# PowerSupply.net
KiCad netlist of a schematic drawn in EAGLE
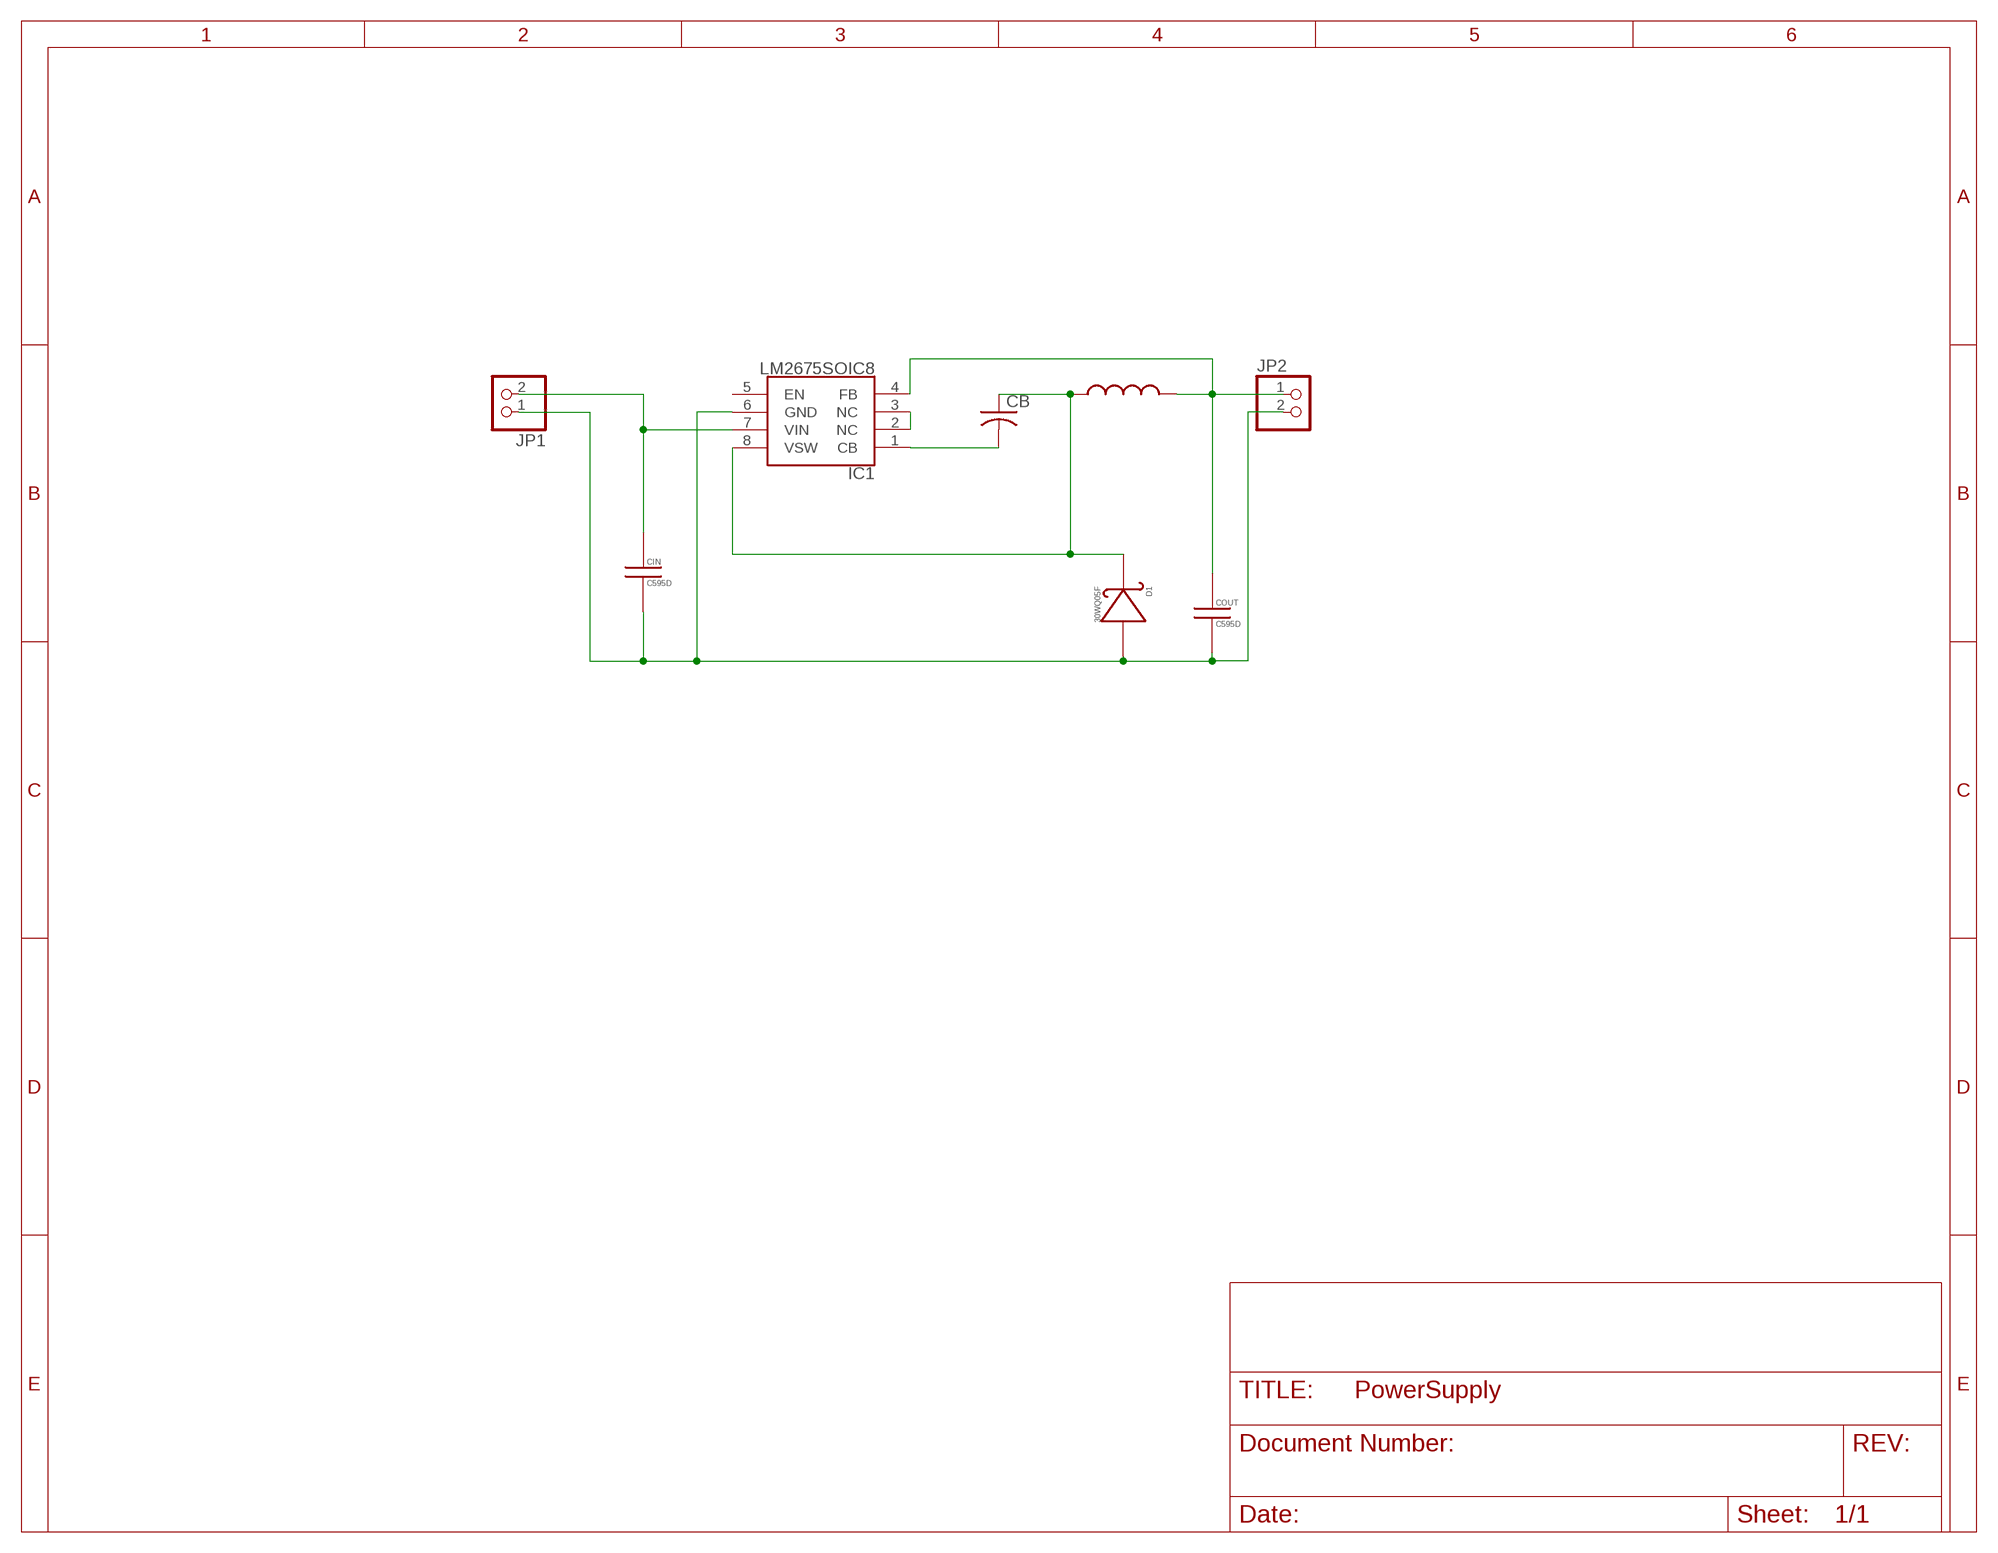
[diagram p0: schematic, sheet 1]

(export (version "E")
  (design (tool "Eeschema 10.0.6"))
  (components
    (comp (ref "CB")
      (value "0.01uF")
      (footprint "eagle-import:C1206")
      (libsource (lib "eagle-import") (part "C-USC1206"))
    )
    (comp (ref "CIN")
      (value "C595D")
      (footprint "eagle-import:C_595D")
      (libsource (lib "eagle-import") (part "C595D"))
    )
    (comp (ref "COUT")
      (value "C595D")
      (footprint "eagle-import:C_595D")
      (libsource (lib "eagle-import") (part "C595D"))
    )
    (comp (ref "D1")
      (value "30WQ05F")
      (footprint "eagle-import:D_SMA")
      (libsource (lib "eagle-import") (part "30WQ05F"))
    )
    (comp (ref "IC1")
      (value "LM2675SOIC8")
      (footprint "eagle-import:SO8")
      (libsource (lib "eagle-import") (part "LM2675SOIC8"))
    )
    (comp (ref "JP1")
      (value "PINHD-1X2")
      (footprint "eagle-import:1X02")
      (libsource (lib "eagle-import") (part "PINHD-1X2"))
    )
    (comp (ref "JP2")
      (value "PINHD-1X2")
      (footprint "eagle-import:1X02")
      (libsource (lib "eagle-import") (part "PINHD-1X2"))
    )
    (comp (ref "L")
      (value "SDR1005L_SMD_V")
      (footprint "eagle-import:L_SMD")
      (libsource (lib "eagle-import") (part "SDR1005L_SMD_V"))
    )
  )
  (nets
    (net (code "1") (name "Net-(IC1-CB)") (class "Default")
      (node (ref "CB") (pin "2") (pinfunction "2_2") (pintype "passive"))
      (node (ref "IC1") (pin "1") (pinfunction "CB_1") (pintype "bidirectional"))
    )
    (net (code "2") (name "Net-(IC1-FB)") (class "Default")
      (node (ref "COUT") (pin "P$2") (pinfunction "P$2_P$2") (pintype "bidirectional"))
      (node (ref "IC1") (pin "4") (pinfunction "FB_4") (pintype "bidirectional"))
      (node (ref "JP2") (pin "1") (pinfunction "1_1") (pintype "passive"))
      (node (ref "L") (pin "P$1") (pinfunction "P$1_P$1") (pintype "bidirectional"))
    )
    (net (code "3") (name "Net-(IC1-GND)") (class "Default")
      (node (ref "CIN") (pin "P$1") (pinfunction "P$1_P$1") (pintype "bidirectional"))
      (node (ref "COUT") (pin "P$1") (pinfunction "P$1_P$1") (pintype "bidirectional"))
      (node (ref "D1") (pin "P$1") (pinfunction "P$1_P$1") (pintype "bidirectional"))
      (node (ref "IC1") (pin "6") (pinfunction "GND_6") (pintype "bidirectional"))
      (node (ref "JP1") (pin "1") (pinfunction "1_1") (pintype "passive"))
      (node (ref "JP2") (pin "2") (pinfunction "2_2") (pintype "passive"))
    )
    (net (code "4") (name "Net-(IC1-NC-Pad2)") (class "Default")
      (node (ref "IC1") (pin "2") (pinfunction "NC_2") (pintype "bidirectional"))
      (node (ref "IC1") (pin "3") (pinfunction "NC_3") (pintype "bidirectional"))
    )
    (net (code "5") (name "Net-(IC1-VIN)") (class "Default")
      (node (ref "CIN") (pin "P$2") (pinfunction "P$2_P$2") (pintype "bidirectional"))
      (node (ref "IC1") (pin "7") (pinfunction "VIN_7") (pintype "bidirectional"))
      (node (ref "JP1") (pin "2") (pinfunction "2_2") (pintype "passive"))
    )
    (net (code "6") (name "Net-(IC1-VSW)") (class "Default")
      (node (ref "CB") (pin "1") (pinfunction "1_1") (pintype "passive"))
      (node (ref "D1") (pin "P$2") (pinfunction "P$2_P$2") (pintype "bidirectional"))
      (node (ref "IC1") (pin "8") (pinfunction "VSW_8") (pintype "bidirectional"))
      (node (ref "L") (pin "P$2") (pinfunction "P$2_P$2") (pintype "bidirectional"))
    )
    (net (code "7") (name "unconnected-(IC1-EN-Pad5)") (class "Default")
      (node (ref "IC1") (pin "5") (pinfunction "EN_5") (pintype "bidirectional"))
    )
  )
)
